# Power.net
KiCad netlist of a schematic drawn in Altium Designer
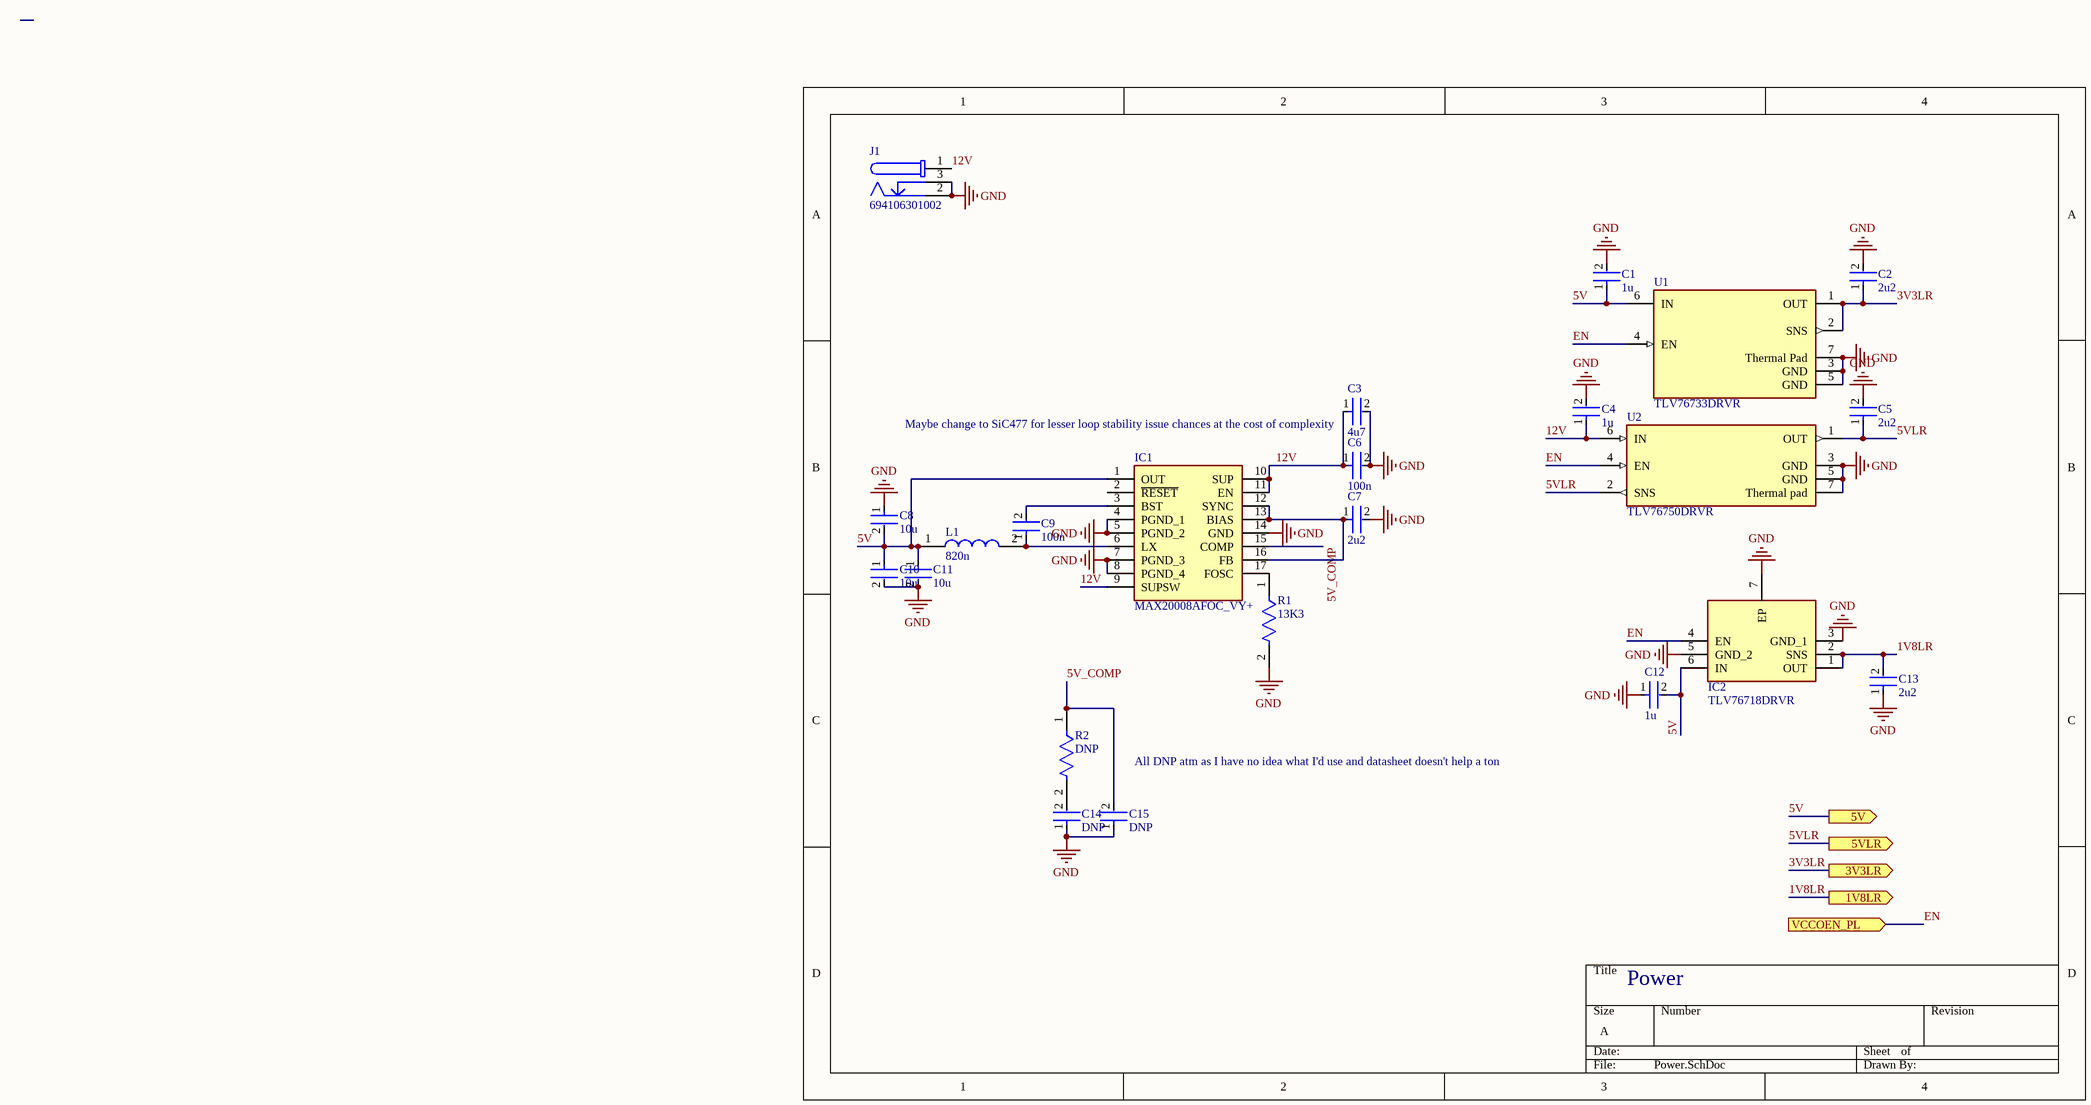
[diagram p0: Power.SchDoc]

(export (version "E")
  (design (tool "Eeschema 10.0.6"))
  (components
    (comp (ref "C1")
      (value "1u")
      (footprint "FP-GRM155-0_1-MFG")
      (description "Chip Multilayer Ceramic Capacitors for General Purpose, 0402, 1.0uF, X5R, 15%, 10%, 50V")
      (libsource (lib "Altium Content Vault") (part "11868f565c42a9108669ba33697ecf6"))
    )
    (comp (ref "C2")
      (value "2u2")
      (footprint "FP-GRM155-0_2-MFG")
      (description "Chip Multilayer Ceramic Capacitors for General Purpose, 0402, 2.2uF, X5R, 15%, 10%, 35V")
      (libsource (lib "Altium Content Vault") (part "b4654b650e69147ec39a6b967a45e02"))
    )
    (comp (ref "C3")
      (value "4u7")
      (footprint "FP-GRT188-0_2-IPC_A")
      (description "Multi-Layer Ceramic Capacitor 4.7uF 35V X5R ±10% 0603 Paper T/R")
      (libsource (lib "Altium Content Vault") (part "02cd4be3c70576c341d710602a673aa"))
    )
    (comp (ref "C4")
      (value "1u")
      (footprint "FP-GRM155-0_1-MFG")
      (description "Chip Multilayer Ceramic Capacitors for General Purpose, 0402, 1.0uF, X5R, 15%, 10%, 50V")
      (libsource (lib "Altium Content Vault") (part "11868f565c42a9108669ba33697ecf6"))
    )
    (comp (ref "C5")
      (value "2u2")
      (footprint "FP-GRM155-0_2-MFG")
      (description "Chip Multilayer Ceramic Capacitors for General Purpose, 0402, 2.2uF, X5R, 15%, 10%, 35V")
      (libsource (lib "Altium Content Vault") (part "b4654b650e69147ec39a6b967a45e02"))
    )
    (comp (ref "C6")
      (value "100n")
      (footprint "FP-GRM155-0_05-IPC_C")
      (description "Chip Multilayer Ceramic Capacitors for General Purpose, 0402, 0.10uF, X5R, 15%, 10%, 100V")
      (fields (field (name "TOLERANCE") "10%"))
      (libsource (lib "Altium Content Vault") (part "02cd4be3c70576c341d710602a673aa"))
    )
    (comp (ref "C7")
      (value "2u2")
      (footprint "FP-GRM155-0_2-MFG")
      (description "Chip Multilayer Ceramic Capacitors for General Purpose, 0402, 2.2uF, X5R, 15%, 10%, 35V")
      (libsource (lib "Altium Content Vault") (part "b4654b650e69147ec39a6b967a45e02"))
    )
    (comp (ref "C8")
      (value "10u")
      (footprint "FP-GRM188-0_2-IPC_B")
      (description "Chip Multilayer Ceramic Capacitors for General Purpose, 0603, 10uF, X5R, 15%, 10%, 25V")
      (libsource (lib "Altium Content Vault") (part "11868f565c42a9108669ba33697ecf6"))
    )
    (comp (ref "C9")
      (value "100n")
      (footprint "FP-GRM155-0_05-IPC_C")
      (description "Chip Multilayer Ceramic Capacitors for General Purpose, 0402, 0.10uF, X5R, 15%, 10%, 100V")
      (fields (field (name "TOLERANCE") "10%"))
      (libsource (lib "Altium Content Vault") (part "02cd4be3c70576c341d710602a673aa"))
    )
    (comp (ref "C10")
      (value "10u")
      (footprint "FP-GRM188-0_2-IPC_B")
      (description "Chip Multilayer Ceramic Capacitors for General Purpose, 0603, 10uF, X5R, 15%, 10%, 25V")
      (libsource (lib "Altium Content Vault") (part "11868f565c42a9108669ba33697ecf6"))
    )
    (comp (ref "C11")
      (value "10u")
      (footprint "FP-GRM188-0_2-IPC_B")
      (description "Chip Multilayer Ceramic Capacitors for General Purpose, 0603, 10uF, X5R, 15%, 10%, 25V")
      (libsource (lib "Altium Content Vault") (part "11868f565c42a9108669ba33697ecf6"))
    )
    (comp (ref "C12")
      (value "1u")
      (footprint "FP-GRM155-0_1-MFG")
      (description "Chip Multilayer Ceramic Capacitors for General Purpose, 0402, 1.0uF, X5R, 15%, 10%, 50V")
      (libsource (lib "Altium Content Vault") (part "11868f565c42a9108669ba33697ecf6"))
    )
    (comp (ref "C13")
      (value "2u2")
      (footprint "FP-GRM155-0_2-MFG")
      (description "Chip Multilayer Ceramic Capacitors for General Purpose, 0402, 2.2uF, X5R, 15%, 10%, 35V")
      (libsource (lib "Altium Content Vault") (part "b4654b650e69147ec39a6b967a45e02"))
    )
    (comp (ref "C14")
      (value "DNP")
      (footprint "FP-GRM155-0_05-IPC_C")
      (description "Chip Multilayer Ceramic Capacitors for General Purpose, 0402, 0.10uF, X5R, 15%, 10%, 100V")
      (fields (field (name "TOLERANCE") "10%"))
      (libsource (lib "Altium Content Vault") (part "02cd4be3c70576c341d710602a673aa"))
    )
    (comp (ref "C15")
      (value "DNP")
      (footprint "FP-GRM155-0_05-IPC_C")
      (description "Chip Multilayer Ceramic Capacitors for General Purpose, 0402, 0.10uF, X5R, 15%, 10%, 100V")
      (fields (field (name "TOLERANCE") "10%"))
      (libsource (lib "Altium Content Vault") (part "02cd4be3c70576c341d710602a673aa"))
    )
    (comp (ref "IC1")
      (value "MAX20008AFOC_VY+")
      (footprint "SamacSys:MAX20008AFOCVY")
      (description "Integrated Circuit")
      (fields
        (field (name "MANUFACTURER_PART_NUMBER") "MAX20008AFOC/VY+")
        (field (name "MOUSER PART NUMBER") "700-MAX20008AFOC/VY+")
      )
      (libsource (lib "*") (part "MAX20008AFOC_VY+"))
    )
    (comp (ref "IC2")
      (value "TLV76718DRVR")
      (footprint "SamacSys:SON65P200X200X80-7N")
      (description "Integrated Circuit")
      (fields (field (name "MOUSER PART NUMBER") "595-TLV76718DRVR"))
      (libsource (lib "*") (part "TLV76718DRVR"))
    )
    (comp (ref "J1")
      (value "694106301002")
      (footprint "694106301002")
      (libsource (lib "Altium Content Vault") (part "DC Power Jack"))
    )
    (comp (ref "L1")
      (value "820n")
      (footprint "SamacSys:INDPM7166X300N")
      (description "Inductor")
      (fields
        (field (name "MANUFACTURER_PART_NUMBER") "ECS-MPIL0630-R82MC")
        (field (name "MOUSER PART NUMBER") "520-MPIL0630-R82MC")
      )
      (libsource (lib "*") (part "ECS-MPIL0630-R82MC"))
    )
    (comp (ref "R1")
      (value "13K3")
      (footprint "FP-AC0402-IPC_B")
      (description "RES 13.3kΩ ±1% 0.063W 0402")
      (fields (field (name "TOLERANCE") "1%"))
      (libsource (lib "Altium Content Vault") (part "1029c3af85768c4190bb7ad29bc67b5"))
    )
    (comp (ref "R2")
      (value "DNP")
      (footprint "FP-AC0402-IPC_B")
      (description "RES 13.3kΩ ±1% 0.063W 0402")
      (fields (field (name "TOLERANCE") "1%"))
      (libsource (lib "Altium Content Vault") (part "1029c3af85768c4190bb7ad29bc67b5"))
    )
    (comp (ref "U1")
      (value "TLV76733DRVR")
      (footprint "FP-DRV0006A-IPC_C")
      (description "VOLTAGE COMPARATOR")
      (libsource (lib "Altium Content Vault") (part "527f072e48108a7b9f646086bfc5874"))
    )
    (comp (ref "U2")
      (value "TLV76750DRVR")
      (footprint "FP-DRV0006A-IPC_B")
      (description "IC VREG LINEAR")
      (libsource (lib "Altium Content Vault") (part "10b8181a2b876d80390fcb7bccd32fe"))
    )
  )
  (nets
    (net (code "1") (name "/1V8LR") (class "Default")
      (node (ref "C13") (pin "2") (pinfunction "2_2") (pintype "passive"))
      (node (ref "IC2") (pin "1") (pinfunction "OUT_1") (pintype "passive"))
      (node (ref "IC2") (pin "2") (pinfunction "SNS_2") (pintype "passive"))
    )
    (net (code "2") (name "/3V3LR") (class "Default")
      (node (ref "C2") (pin "1") (pinfunction "1_1") (pintype "passive"))
      (node (ref "U1") (pin "1") (pinfunction "OUT_1") (pintype "passive"))
      (node (ref "U1") (pin "2") (pinfunction "SNS_2") (pintype "output"))
    )
    (net (code "3") (name "/5V") (class "Default")
      (node (ref "C1") (pin "1") (pinfunction "1_1") (pintype "passive"))
      (node (ref "C10") (pin "1") (pinfunction "1_1") (pintype "passive"))
      (node (ref "C11") (pin "1") (pinfunction "1_1") (pintype "passive"))
      (node (ref "C12") (pin "2") (pinfunction "2_2") (pintype "passive"))
      (node (ref "C8") (pin "2") (pinfunction "2_2") (pintype "passive"))
      (node (ref "IC1") (pin "1") (pinfunction "OUT_1") (pintype "passive"))
      (node (ref "IC2") (pin "6") (pinfunction "IN_6") (pintype "passive"))
      (node (ref "L1") (pin "1") (pinfunction "1_1") (pintype "passive"))
      (node (ref "U1") (pin "6") (pinfunction "IN_6") (pintype "power_in"))
    )
    (net (code "4") (name "/5VLR") (class "Default")
      (node (ref "C5") (pin "1") (pinfunction "1_1") (pintype "passive"))
      (node (ref "U2") (pin "1") (pinfunction "OUT_1") (pintype "output"))
      (node (ref "U2") (pin "2") (pinfunction "SNS_2") (pintype "output"))
    )
    (net (code "5") (name "/5V_COMP") (class "Default")
      (node (ref "C15") (pin "2") (pinfunction "2_2") (pintype "passive"))
      (node (ref "IC1") (pin "15") (pinfunction "COMP_15") (pintype "passive"))
      (node (ref "R2") (pin "1") (pinfunction "1_1") (pintype "passive"))
    )
    (net (code "6") (name "/12V") (class "Default")
      (node (ref "C3") (pin "1") (pinfunction "1_1") (pintype "passive"))
      (node (ref "C4") (pin "1") (pinfunction "1_1") (pintype "passive"))
      (node (ref "C6") (pin "1") (pinfunction "1_1") (pintype "passive"))
      (node (ref "IC1") (pin "10") (pinfunction "SUP_10") (pintype "passive"))
      (node (ref "IC1") (pin "11") (pinfunction "EN_11") (pintype "passive"))
      (node (ref "IC1") (pin "9") (pinfunction "SUPSW_9") (pintype "passive"))
      (node (ref "J1") (pin "1") (pinfunction "1_1") (pintype "passive"))
      (node (ref "U2") (pin "6") (pinfunction "IN_6") (pintype "input"))
    )
    (net (code "7") (name "/EN") (class "Default")
      (node (ref "IC2") (pin "4") (pinfunction "EN_4") (pintype "passive"))
      (node (ref "U1") (pin "4") (pinfunction "EN_4") (pintype "input"))
      (node (ref "U2") (pin "4") (pinfunction "EN_4") (pintype "input"))
    )
    (net (code "8") (name "GND") (class "Default")
      (node (ref "C1") (pin "2") (pinfunction "2_2") (pintype "passive"))
      (node (ref "C10") (pin "2") (pinfunction "2_2") (pintype "passive"))
      (node (ref "C11") (pin "2") (pinfunction "2_2") (pintype "passive"))
      (node (ref "C12") (pin "1") (pinfunction "1_1") (pintype "passive"))
      (node (ref "C13") (pin "1") (pinfunction "1_1") (pintype "passive"))
      (node (ref "C14") (pin "1") (pinfunction "1_1") (pintype "passive"))
      (node (ref "C15") (pin "1") (pinfunction "1_1") (pintype "passive"))
      (node (ref "C2") (pin "2") (pinfunction "2_2") (pintype "passive"))
      (node (ref "C3") (pin "2") (pinfunction "2_2") (pintype "passive"))
      (node (ref "C4") (pin "2") (pinfunction "2_2") (pintype "passive"))
      (node (ref "C5") (pin "2") (pinfunction "2_2") (pintype "passive"))
      (node (ref "C6") (pin "2") (pinfunction "2_2") (pintype "passive"))
      (node (ref "C7") (pin "2") (pinfunction "2_2") (pintype "passive"))
      (node (ref "C8") (pin "1") (pinfunction "1_1") (pintype "passive"))
      (node (ref "IC1") (pin "14") (pinfunction "GND_14") (pintype "passive"))
      (node (ref "IC1") (pin "4") (pinfunction "PGND_1_4") (pintype "passive"))
      (node (ref "IC1") (pin "5") (pinfunction "PGND_2_5") (pintype "passive"))
      (node (ref "IC1") (pin "7") (pinfunction "PGND_3_7") (pintype "passive"))
      (node (ref "IC1") (pin "8") (pinfunction "PGND_4_8") (pintype "passive"))
      (node (ref "IC2") (pin "3") (pinfunction "GND_1_3") (pintype "passive"))
      (node (ref "IC2") (pin "5") (pinfunction "GND_2_5") (pintype "passive"))
      (node (ref "IC2") (pin "7") (pinfunction "EP_7") (pintype "passive"))
      (node (ref "J1") (pin "2") (pinfunction "2_2") (pintype "passive"))
      (node (ref "J1") (pin "3") (pinfunction "3_3") (pintype "passive"))
      (node (ref "R1") (pin "2") (pinfunction "2_2") (pintype "passive"))
      (node (ref "U1") (pin "3") (pinfunction "GND_3") (pintype "power_in"))
      (node (ref "U1") (pin "5") (pinfunction "GND_5") (pintype "power_in"))
      (node (ref "U1") (pin "7") (pinfunction "Thermal_Pad_7") (pintype "passive"))
      (node (ref "U2") (pin "3") (pinfunction "GND_3") (pintype "power_in"))
      (node (ref "U2") (pin "5") (pinfunction "GND_5") (pintype "power_in"))
      (node (ref "U2") (pin "7") (pinfunction "Thermal_pad_7") (pintype "passive"))
    )
    (net (code "9") (name "Net-(C14-Pad2)") (class "Default")
      (node (ref "C14") (pin "2") (pinfunction "2_2") (pintype "passive"))
      (node (ref "R2") (pin "2") (pinfunction "2_2") (pintype "passive"))
    )
    (net (code "10") (name "Net-(IC1-BIAS)") (class "Default")
      (node (ref "C7") (pin "1") (pinfunction "1_1") (pintype "passive"))
      (node (ref "IC1") (pin "12") (pinfunction "SYNC_12") (pintype "passive"))
      (node (ref "IC1") (pin "13") (pinfunction "BIAS_13") (pintype "passive"))
      (node (ref "IC1") (pin "16") (pinfunction "FB_16") (pintype "passive"))
    )
    (net (code "11") (name "Net-(IC1-BST)") (class "Default")
      (node (ref "C9") (pin "2") (pinfunction "2_2") (pintype "passive"))
      (node (ref "IC1") (pin "3") (pinfunction "BST_3") (pintype "passive"))
    )
    (net (code "12") (name "Net-(IC1-FOSC)") (class "Default")
      (node (ref "IC1") (pin "17") (pinfunction "FOSC_17") (pintype "passive"))
      (node (ref "R1") (pin "1") (pinfunction "1_1") (pintype "passive"))
    )
    (net (code "13") (name "Net-(IC1-LX)") (class "Default")
      (node (ref "C9") (pin "1") (pinfunction "1_1") (pintype "passive"))
      (node (ref "IC1") (pin "6") (pinfunction "LX_6") (pintype "passive"))
      (node (ref "L1") (pin "2") (pinfunction "2_2") (pintype "passive"))
    )
    (net (code "14") (name "unconnected-(IC1-~{RESET}-Pad2)") (class "Default")
      (node (ref "IC1") (pin "2") (pinfunction "~{RESET}_2") (pintype "passive"))
    )
  )
)
